# motordriver.net
KiCad netlist of a schematic drawn in Altium Designer
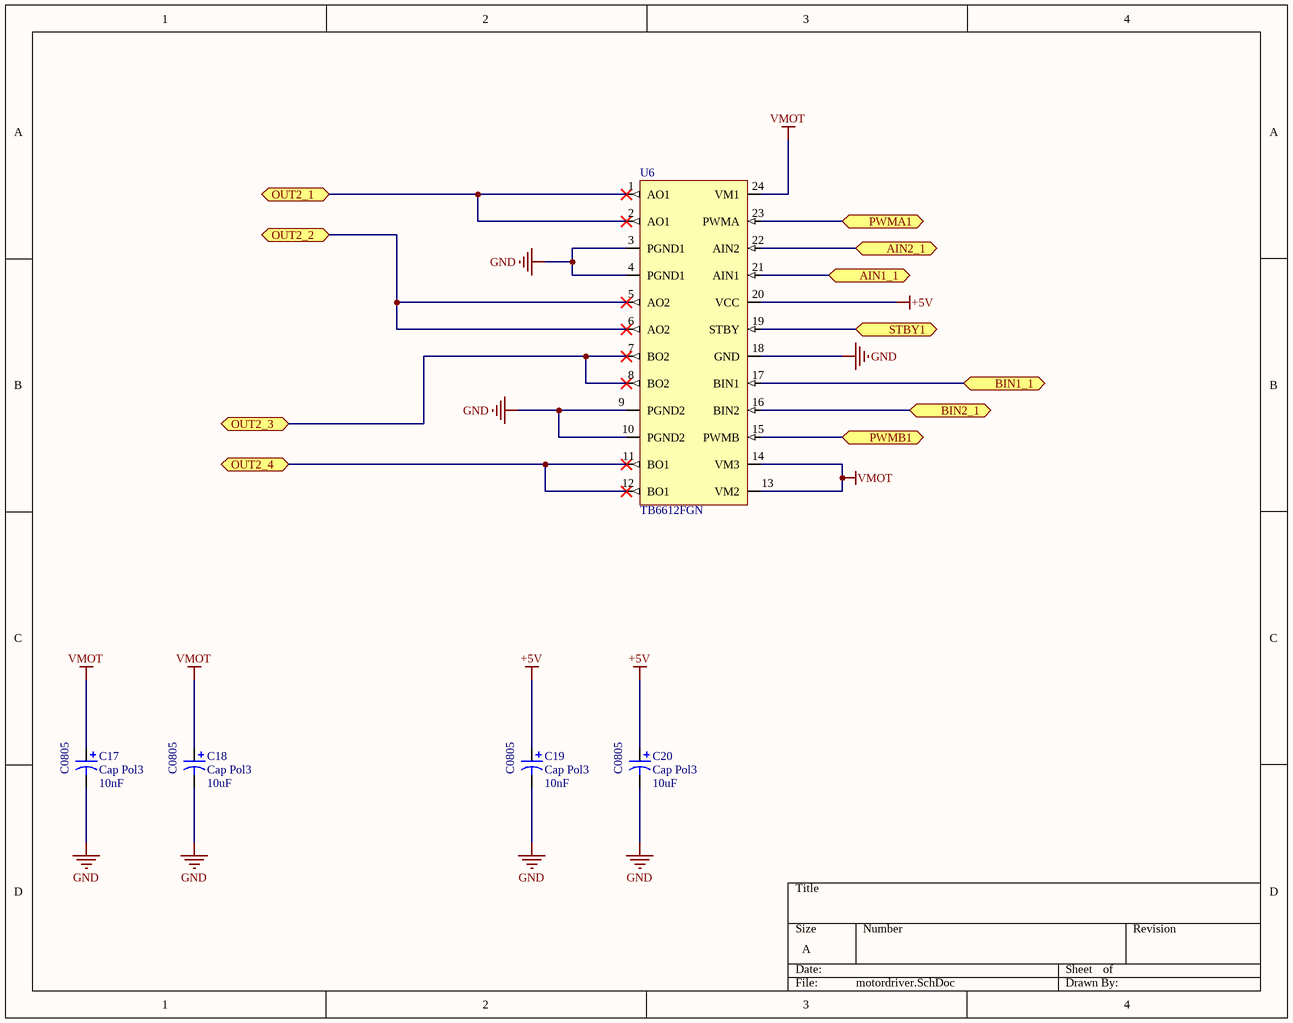
[diagram p0: motordriver.SchDoc]

(export (version "E")
  (design (tool "Eeschema 10.0.6"))
  (components
    (comp (ref "C17")
      (value "Cap Pol3")
      (footprint "C0805")
      (description "Polarized Capacitor (Surface Mount)")
      (fields
        (field (name "PACKAGEREFERENCE") "C0805")
        (field (name "ALTIUM_VALUE") "10nF")
        (field (name "PUBLISHER") "Altium Limited")
      )
      (libsource (lib "Miscellaneous Devices") (part "Cap Pol3"))
    )
    (comp (ref "C18")
      (value "Cap Pol3")
      (footprint "C0805")
      (description "Polarized Capacitor (Surface Mount)")
      (fields
        (field (name "PACKAGEREFERENCE") "C0805")
        (field (name "ALTIUM_VALUE") "10uF")
        (field (name "PUBLISHER") "Altium Limited")
      )
      (libsource (lib "Miscellaneous Devices") (part "Cap Pol3"))
    )
    (comp (ref "C19")
      (value "Cap Pol3")
      (footprint "C0805")
      (description "Polarized Capacitor (Surface Mount)")
      (fields
        (field (name "PACKAGEREFERENCE") "C0805")
        (field (name "ALTIUM_VALUE") "10nF")
        (field (name "PUBLISHER") "Altium Limited")
      )
      (libsource (lib "Miscellaneous Devices") (part "Cap Pol3"))
    )
    (comp (ref "C20")
      (value "Cap Pol3")
      (footprint "C0805")
      (description "Polarized Capacitor (Surface Mount)")
      (fields
        (field (name "PACKAGEREFERENCE") "C0805")
        (field (name "ALTIUM_VALUE") "10uF")
        (field (name "PUBLISHER") "Altium Limited")
      )
      (libsource (lib "Miscellaneous Devices") (part "Cap Pol3"))
    )
    (comp (ref "U6")
      (value "TB6612FGN")
      (footprint "TBS6612FNG")
      (libsource (lib "TB6612FNGSCHLIB") (part "TB6612FGN"))
    )
  )
  (nets
    (net (code "1") (name "+5V") (class "Default")
      (node (ref "C19") (pin "1") (pinfunction "1_1") (pintype "passive"))
      (node (ref "C20") (pin "1") (pinfunction "1_1") (pintype "passive"))
      (node (ref "U6") (pin "20") (pinfunction "VCC_20") (pintype "passive"))
    )
    (net (code "2") (name "/AIN1_1") (class "Default")
      (node (ref "U6") (pin "21") (pinfunction "AIN1_21") (pintype "input"))
    )
    (net (code "3") (name "/AIN2_1") (class "Default")
      (node (ref "U6") (pin "22") (pinfunction "AIN2_22") (pintype "input"))
    )
    (net (code "4") (name "/BIN1_1") (class "Default")
      (node (ref "U6") (pin "17") (pinfunction "BIN1_17") (pintype "input"))
    )
    (net (code "5") (name "/BIN2_1") (class "Default")
      (node (ref "U6") (pin "16") (pinfunction "BIN2_16") (pintype "input"))
    )
    (net (code "6") (name "/OUT2_1") (class "Default")
      (node (ref "U6") (pin "1") (pinfunction "AO1_1") (pintype "output"))
      (node (ref "U6") (pin "2") (pinfunction "AO1_2") (pintype "output"))
    )
    (net (code "7") (name "/OUT2_2") (class "Default")
      (node (ref "U6") (pin "5") (pinfunction "AO2_5") (pintype "output"))
      (node (ref "U6") (pin "6") (pinfunction "AO2_6") (pintype "output"))
    )
    (net (code "8") (name "/OUT2_3") (class "Default")
      (node (ref "U6") (pin "7") (pinfunction "BO2_7") (pintype "output"))
      (node (ref "U6") (pin "8") (pinfunction "BO2_8") (pintype "output"))
    )
    (net (code "9") (name "/OUT2_4") (class "Default")
      (node (ref "U6") (pin "11") (pinfunction "BO1_11") (pintype "output"))
      (node (ref "U6") (pin "12") (pinfunction "BO1_12") (pintype "output"))
    )
    (net (code "10") (name "/PWMA1") (class "Default")
      (node (ref "U6") (pin "23") (pinfunction "PWMA_23") (pintype "input"))
    )
    (net (code "11") (name "/PWMB1") (class "Default")
      (node (ref "U6") (pin "15") (pinfunction "PWMB_15") (pintype "input"))
    )
    (net (code "12") (name "/STBY1") (class "Default")
      (node (ref "U6") (pin "19") (pinfunction "STBY_19") (pintype "input"))
    )
    (net (code "13") (name "GND") (class "Default")
      (node (ref "C17") (pin "2") (pinfunction "2_2") (pintype "passive"))
      (node (ref "C18") (pin "2") (pinfunction "2_2") (pintype "passive"))
      (node (ref "C19") (pin "2") (pinfunction "2_2") (pintype "passive"))
      (node (ref "C20") (pin "2") (pinfunction "2_2") (pintype "passive"))
      (node (ref "U6") (pin "10") (pinfunction "PGND2_10") (pintype "passive"))
      (node (ref "U6") (pin "18") (pinfunction "GND_18") (pintype "passive"))
      (node (ref "U6") (pin "3") (pinfunction "PGND1_3") (pintype "passive"))
      (node (ref "U6") (pin "4") (pinfunction "PGND1_4") (pintype "passive"))
      (node (ref "U6") (pin "9") (pinfunction "PGND2_9") (pintype "passive"))
    )
    (net (code "14") (name "VMOT") (class "Default")
      (node (ref "C17") (pin "1") (pinfunction "1_1") (pintype "passive"))
      (node (ref "C18") (pin "1") (pinfunction "1_1") (pintype "passive"))
      (node (ref "U6") (pin "13") (pinfunction "VM2_13") (pintype "passive"))
      (node (ref "U6") (pin "14") (pinfunction "VM3_14") (pintype "passive"))
      (node (ref "U6") (pin "24") (pinfunction "VM1_24") (pintype "passive"))
    )
  )
)
